# SUPPLY.net
KiCad netlist of a schematic drawn in Altium Designer
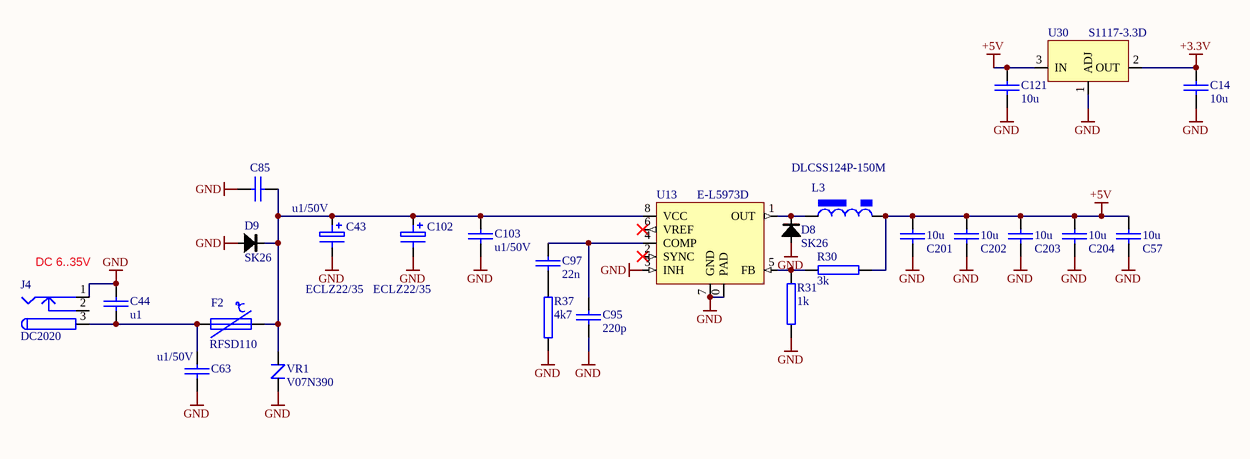
[diagram p0: SUPPLY.SchDoc]

(export (version "E")
  (design (tool "Eeschema 10.0.6"))
  (components
    (comp (ref "C14")
      (value "10u")
      (footprint "0805")
      (description "Capacitor SMD")
      (libsource (lib "*") (part "CAP_SMD"))
    )
    (comp (ref "C43")
      (value "ECLZ22/35")
      (footprint "CAP_SMT_EL_6.3mm_D")
      (description "Electrolytic Capacitor")
      (libsource (lib "*") (part "CAP_ELECTRO_SMD"))
    )
    (comp (ref "C44")
      (value "u1")
      (footprint "0603")
      (description "Capacitor SMD")
      (libsource (lib "LIBRARY_SCH") (part "CAP_SMD"))
    )
    (comp (ref "C57")
      (value "10u")
      (footprint "0805C")
      (description "Capacitor SMD")
      (libsource (lib "LIBRARY_SCH") (part "CAP_SMD"))
    )
    (comp (ref "C63")
      (value "u1/50V")
      (footprint "0805C")
      (description "Capacitor SMD")
      (libsource (lib "LIBRARY_SCH") (part "CAP_SMD"))
    )
    (comp (ref "C85")
      (value "u1/50V")
      (footprint "0805C")
      (description "Capacitor SMD")
      (libsource (lib "LIBRARY_SCH") (part "CAP_SMD"))
    )
    (comp (ref "C95")
      (value "220p")
      (footprint "0603C")
      (description "Capacitor SMD")
      (libsource (lib "LIBRARY_SCH") (part "CAP_SMD"))
    )
    (comp (ref "C97")
      (value "22n")
      (footprint "0603C")
      (description "Capacitor SMD")
      (libsource (lib "LIBRARY_SCH") (part "CAP_SMD"))
    )
    (comp (ref "C102")
      (value "ECLZ22/35")
      (footprint "CAP_SMT_EL_6.3mm_D")
      (description "Electrolytic Capacitor")
      (libsource (lib "*") (part "CAP_ELECTRO_SMD"))
    )
    (comp (ref "C103")
      (value "u1/50V")
      (footprint "0805C")
      (description "Capacitor SMD")
      (libsource (lib "LIBRARY_SCH") (part "CAP_SMD"))
    )
    (comp (ref "C121")
      (value "10u")
      (footprint "0805")
      (description "Capacitor SMD")
      (libsource (lib "*") (part "CAP_SMD"))
    )
    (comp (ref "C201")
      (value "10u")
      (footprint "0805C")
      (description "Capacitor SMD")
      (libsource (lib "LIBRARY_SCH") (part "CAP_SMD"))
    )
    (comp (ref "C202")
      (value "10u")
      (footprint "0805C")
      (description "Capacitor SMD")
      (libsource (lib "LIBRARY_SCH") (part "CAP_SMD"))
    )
    (comp (ref "C203")
      (value "10u")
      (footprint "0805C")
      (description "Capacitor SMD")
      (libsource (lib "LIBRARY_SCH") (part "CAP_SMD"))
    )
    (comp (ref "C204")
      (value "10u")
      (footprint "0805C")
      (description "Capacitor SMD")
      (libsource (lib "LIBRARY_SCH") (part "CAP_SMD"))
    )
    (comp (ref "D8")
      (value "SK26")
      (footprint "DO-214AA/SMB")
      (description "2A shottky diode (Maritex)")
      (libsource (lib "") (part "DIODE_SK26_1"))
    )
    (comp (ref "D9")
      (value "SK26")
      (footprint "DO-214AA/SMB")
      (description "2A shottky diode (Maritex)")
      (libsource (lib "LIBRARY_SCH") (part "DIODE_SK26"))
    )
    (comp (ref "F2")
      (value "RFSD110")
      (footprint "PTC_SMD_1812")
      (description "polymer FUSE")
      (libsource (lib "LIBRARY_SCH") (part "F_POLYSWITCH"))
    )
    (comp (ref "J4")
      (value "DC2020")
      (footprint "DC2020")
      (description "Low Voltage Power Supply Connector (maritex)")
      (fields (field (name "PUBLISHER") "Altium Limited"))
      (libsource (lib "LIBRARY_SCH") (part "CON_DC_JACK_TH"))
    )
    (comp (ref "L3")
      (value "DLCSS124P-150M")
      (footprint "choke_DLCSS124")
      (description "inductor")
      (libsource (lib "LIBRARY_SCH") (part "POWER_INDUCTOR_CSS124"))
    )
    (comp (ref "R30")
      (value "3k")
      (footprint "0603R")
      (description "SMD Resistor")
      (libsource (lib "LIBRARY_SCH") (part "RES_SMD"))
    )
    (comp (ref "R31")
      (value "1k")
      (footprint "0603R")
      (description "SMD Resistor")
      (libsource (lib "LIBRARY_SCH") (part "RES_SMD"))
    )
    (comp (ref "R37")
      (value "4k7")
      (footprint "0603R")
      (description "SMD Resistor")
      (libsource (lib "LIBRARY_SCH") (part "RES_SMD"))
    )
    (comp (ref "U13")
      (value "E-L5973D")
      (footprint "PDSO-8")
      (description "2.5A SWITCH STEP DOWN SWITCHING REGULATOR")
      (libsource (lib "LIBRARY_SCH") (part "L5973D"))
    )
    (comp (ref "U30")
      (value "S1117-3.3D")
      (footprint "TO-252")
      (description "Voltage Regulator")
      (libsource (lib "LIBRARY_SCH") (part "REG_S1117-3.3D"))
    )
    (comp (ref "VR1")
      (value "V07N390")
      (footprint "Varistor_7mm")
      (description "varistor 7mm (Maritex)")
      (libsource (lib "LIBRARY_SCH") (part "Varistor V07N"))
    )
  )
  (nets
    (net (code "1") (name "+3.3V") (class "Default")
      (node (ref "C14") (pin "2") (pinfunction "2_2") (pintype "passive"))
      (node (ref "U30") (pin "2") (pinfunction "OUT_2") (pintype "passive"))
    )
    (net (code "2") (name "+5V") (class "Default")
      (node (ref "C121") (pin "2") (pinfunction "2_2") (pintype "passive"))
      (node (ref "C201") (pin "1") (pinfunction "1_1") (pintype "passive"))
      (node (ref "C202") (pin "1") (pinfunction "1_1") (pintype "passive"))
      (node (ref "C203") (pin "1") (pinfunction "1_1") (pintype "passive"))
      (node (ref "C204") (pin "1") (pinfunction "1_1") (pintype "passive"))
      (node (ref "C57") (pin "1") (pinfunction "1_1") (pintype "passive"))
      (node (ref "L3") (pin "2") (pintype "passive"))
      (node (ref "R30") (pin "1") (pinfunction "1_1") (pintype "passive"))
      (node (ref "U30") (pin "3") (pinfunction "IN_3") (pintype "passive"))
    )
    (net (code "3") (name "GND") (class "Default")
      (node (ref "C102") (pin "2") (pinfunction "2_2") (pintype "passive"))
      (node (ref "C103") (pin "2") (pinfunction "2_2") (pintype "passive"))
      (node (ref "C121") (pin "1") (pinfunction "1_1") (pintype "passive"))
      (node (ref "C14") (pin "1") (pinfunction "1_1") (pintype "passive"))
      (node (ref "C201") (pin "2") (pinfunction "2_2") (pintype "passive"))
      (node (ref "C202") (pin "2") (pinfunction "2_2") (pintype "passive"))
      (node (ref "C203") (pin "2") (pinfunction "2_2") (pintype "passive"))
      (node (ref "C204") (pin "2") (pinfunction "2_2") (pintype "passive"))
      (node (ref "C43") (pin "2") (pinfunction "2_2") (pintype "passive"))
      (node (ref "C44") (pin "1") (pinfunction "1_1") (pintype "passive"))
      (node (ref "C57") (pin "2") (pinfunction "2_2") (pintype "passive"))
      (node (ref "C63") (pin "2") (pinfunction "2_2") (pintype "passive"))
      (node (ref "C85") (pin "2") (pinfunction "2_2") (pintype "passive"))
      (node (ref "C95") (pin "1") (pinfunction "1_1") (pintype "passive"))
      (node (ref "D8") (pin "A") (pinfunction "A_A") (pintype "passive"))
      (node (ref "D9") (pin "A") (pinfunction "A_A") (pintype "passive"))
      (node (ref "J4") (pin "1") (pintype "power_in"))
      (node (ref "R31") (pin "2") (pinfunction "2_2") (pintype "passive"))
      (node (ref "R37") (pin "1") (pinfunction "1_1") (pintype "passive"))
      (node (ref "U13") (pin "0") (pinfunction "PAD_0") (pintype "passive"))
      (node (ref "U13") (pin "3") (pinfunction "INH_3") (pintype "input"))
      (node (ref "U13") (pin "7") (pinfunction "GND_7") (pintype "power_in"))
      (node (ref "U30") (pin "1") (pinfunction "ADJ_1") (pintype "passive"))
      (node (ref "VR1") (pin "2") (pinfunction "2_2") (pintype "power_in"))
    )
    (net (code "4") (name "Net-(C44-Pad2)") (class "Default")
      (node (ref "C44") (pin "2") (pinfunction "2_2") (pintype "passive"))
      (node (ref "C63") (pin "1") (pinfunction "1_1") (pintype "passive"))
      (node (ref "F2") (pin "1") (pinfunction "1_1") (pintype "passive"))
      (node (ref "J4") (pin "3") (pintype "power_in"))
    )
    (net (code "5") (name "Net-(C97-Pad1)") (class "Default")
      (node (ref "C97") (pin "1") (pinfunction "1_1") (pintype "passive"))
      (node (ref "R37") (pin "2") (pinfunction "2_2") (pintype "passive"))
    )
    (net (code "6") (name "Net-(U13-COMP)") (class "Default")
      (node (ref "C95") (pin "2") (pinfunction "2_2") (pintype "passive"))
      (node (ref "C97") (pin "2") (pinfunction "2_2") (pintype "passive"))
      (node (ref "U13") (pin "4") (pinfunction "COMP_4") (pintype "passive"))
    )
    (net (code "7") (name "Net-(U13-FB)") (class "Default")
      (node (ref "R30") (pin "2") (pinfunction "2_2") (pintype "passive"))
      (node (ref "R31") (pin "1") (pinfunction "1_1") (pintype "passive"))
      (node (ref "U13") (pin "5") (pinfunction "FB_5") (pintype "input"))
    )
    (net (code "8") (name "Net-(U13-OUT)") (class "Default")
      (node (ref "D8") (pin "K") (pinfunction "K_K") (pintype "passive"))
      (node (ref "L3") (pin "1") (pintype "passive"))
      (node (ref "U13") (pin "1") (pinfunction "OUT_1") (pintype "output"))
    )
    (net (code "9") (name "Net-(U13-VCC)") (class "Default")
      (node (ref "C102") (pin "1") (pinfunction "1_1") (pintype "passive"))
      (node (ref "C103") (pin "1") (pinfunction "1_1") (pintype "passive"))
      (node (ref "C43") (pin "1") (pinfunction "1_1") (pintype "passive"))
      (node (ref "C85") (pin "1") (pinfunction "1_1") (pintype "passive"))
      (node (ref "D9") (pin "K") (pinfunction "K_K") (pintype "passive"))
      (node (ref "F2") (pin "2") (pinfunction "2_2") (pintype "passive"))
      (node (ref "U13") (pin "8") (pinfunction "VCC_8") (pintype "power_in"))
      (node (ref "VR1") (pin "1") (pinfunction "1_1") (pintype "power_in"))
    )
    (net (code "10") (name "unconnected-(J4-Pad2)") (class "Default")
      (node (ref "J4") (pin "2") (pintype "power_in"))
    )
    (net (code "11") (name "unconnected-(U13-SYNC-Pad2)") (class "Default")
      (node (ref "U13") (pin "2") (pinfunction "SYNC_2") (pintype "input+no_connect"))
    )
    (net (code "12") (name "unconnected-(U13-VREF-Pad6)") (class "Default")
      (node (ref "U13") (pin "6") (pinfunction "VREF_6") (pintype "output+no_connect"))
    )
  )
)
